# YTN1-E608_Key.net
KiCad netlist of a schematic drawn in Altium Designer
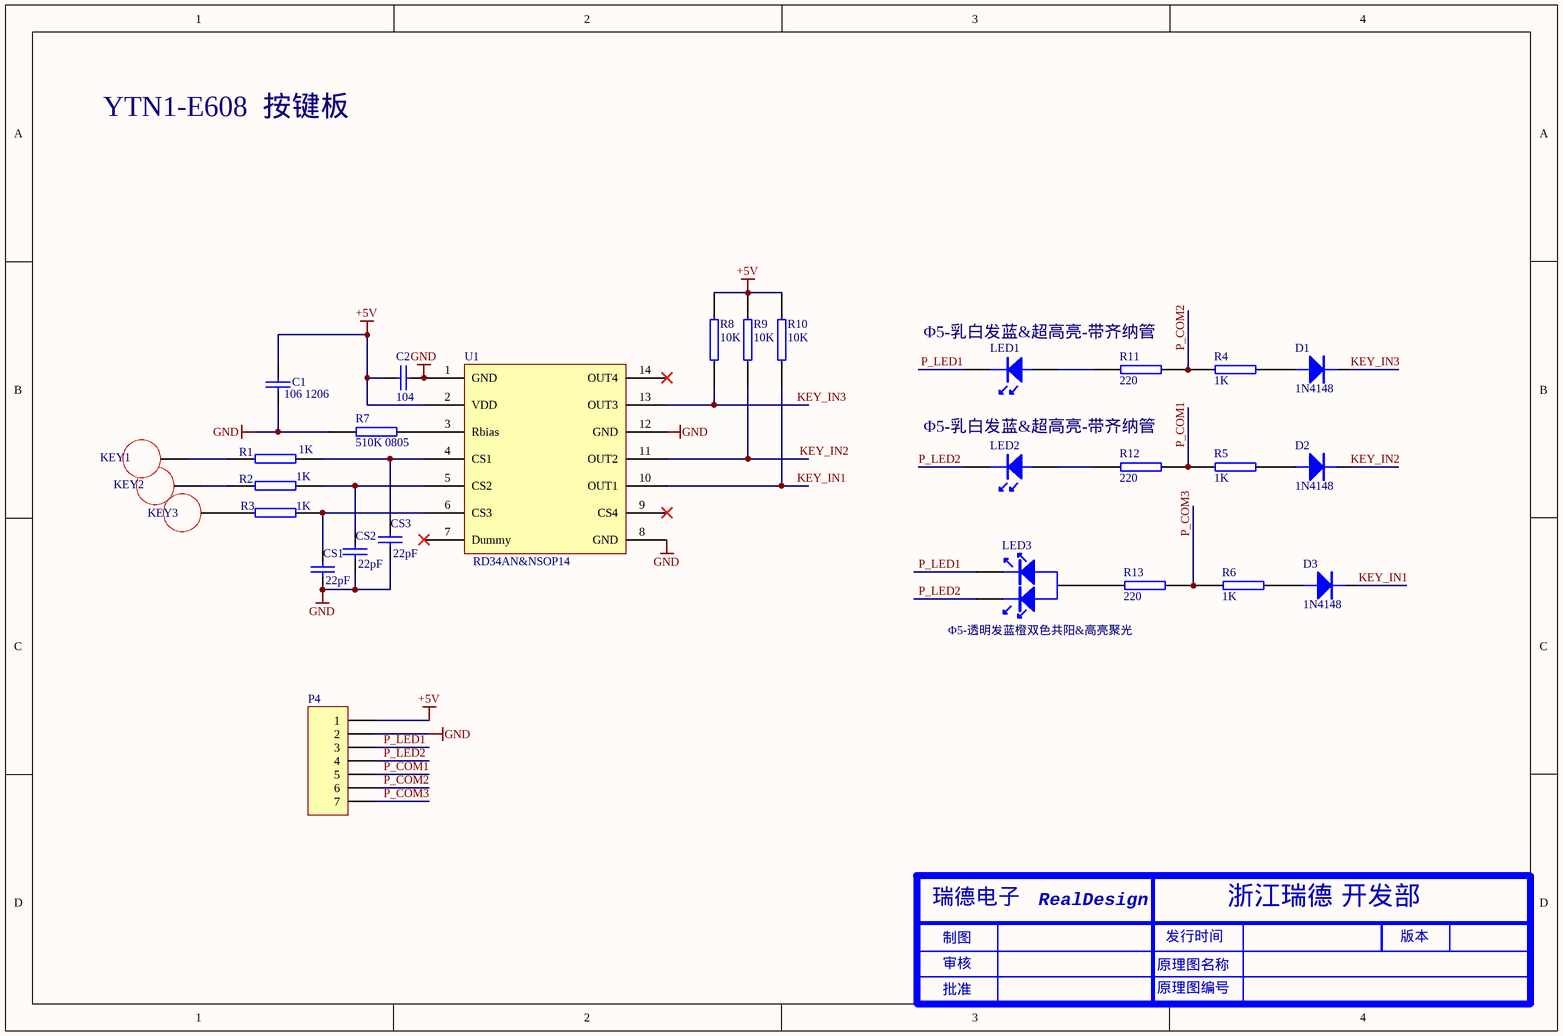
[diagram p0: YTN1-E608(Key)按键板..schdoc]

(export (version "E")
  (design (tool "Eeschema 10.0.6"))
  (components
    (comp (ref "C1") (value "106 1206") (libsource (lib "*") (part "CAP")))
    (comp (ref "C2") (value "104") (libsource (lib "*") (part "CAP")))
    (comp (ref "CS1") (value "22pF") (libsource (lib "*") (part "CAP")))
    (comp (ref "CS2") (value "22pF") (libsource (lib "*") (part "CAP")))
    (comp (ref "CS3") (value "22pF") (libsource (lib "*") (part "CAP")))
    (comp (ref "D1") (value "1N4148") (libsource (lib "*") (part "D4007")))
    (comp (ref "D2") (value "1N4148") (libsource (lib "*") (part "D4007")))
    (comp (ref "D3") (value "1N4148") (libsource (lib "*") (part "D4007")))
    (comp (ref "KEY1") (value "~") (footprint "7130A-K") (libsource (lib "*") (part "TPAD-2")))
    (comp (ref "KEY2") (value "~") (footprint "7130A-K") (libsource (lib "*") (part "TPAD-2")))
    (comp (ref "KEY3") (value "~") (footprint "7130A-K") (libsource (lib "*") (part "TPAD-2")))
    (comp (ref "LED1") (value "~") (footprint "LED5.0-AI1") (libsource (lib "*") (part "LED")))
    (comp (ref "LED2") (value "~") (footprint "LED5.0-AI1") (libsource (lib "*") (part "LED")))
    (comp (ref "LED3") (value "Φ5-透明发蓝橙双色共阳&高亮聚光") (libsource (lib "*") (part "共阳双色发光二极管")))
    (comp (ref "P4")
      (value "~")
      (footprint "HDR1X7")
      (description "Header, 7-Pin")
      (fields (field (name "PUBLISHER") "Altium Limited"))
      (libsource (lib "*") (part "Header 7"))
    )
    (comp (ref "R1") (value "1K") (libsource (lib "*") (part "R")))
    (comp (ref "R2") (value "1K") (libsource (lib "*") (part "R")))
    (comp (ref "R3") (value "1K") (libsource (lib "*") (part "R")))
    (comp (ref "R4") (value "1K") (libsource (lib "*") (part "R")))
    (comp (ref "R5") (value "1K") (libsource (lib "*") (part "R")))
    (comp (ref "R6") (value "1K") (libsource (lib "*") (part "R")))
    (comp (ref "R7") (value "510K 0805") (libsource (lib "*") (part "R")))
    (comp (ref "R8") (value "10K") (libsource (lib "*") (part "R")))
    (comp (ref "R9") (value "10K") (libsource (lib "*") (part "R")))
    (comp (ref "R10") (value "10K") (libsource (lib "*") (part "R")))
    (comp (ref "R11") (value "220") (libsource (lib "*") (part "RES2")))
    (comp (ref "R12") (value "220") (libsource (lib "*") (part "RES2")))
    (comp (ref "R13") (value "220") (libsource (lib "*") (part "R")))
    (comp (ref "U1")
      (value "RD34AN&NSOP14")
      (footprint "SOP14")
      (description "HT48R06A-1(16PIN)")
      (libsource (lib "*") (part "HT48R06A-1(16PIN)"))
    )
  )
  (nets
    (net (code "1") (name "+5V") (class "Default")
      (node (ref "C1") (pin "1") (pintype "passive"))
      (node (ref "C2") (pin "2") (pintype "passive"))
      (node (ref "P4") (pin "1") (pinfunction "1_1") (pintype "passive"))
      (node (ref "R10") (pin "2") (pinfunction "2_2") (pintype "passive"))
      (node (ref "R8") (pin "2") (pinfunction "2_2") (pintype "passive"))
      (node (ref "R9") (pin "2") (pinfunction "2_2") (pintype "passive"))
      (node (ref "U1") (pin "2") (pinfunction "VDD_2") (pintype "passive"))
    )
    (net (code "2") (name "/KEY_IN1") (class "Default")
      (node (ref "D3") (pin "K") (pinfunction "K_K") (pintype "passive"))
      (node (ref "R10") (pin "1") (pinfunction "1_1") (pintype "passive"))
      (node (ref "U1") (pin "10") (pinfunction "OUT1_10") (pintype "passive"))
    )
    (net (code "3") (name "/KEY_IN2") (class "Default")
      (node (ref "D2") (pin "K") (pinfunction "K_K") (pintype "passive"))
      (node (ref "R9") (pin "1") (pinfunction "1_1") (pintype "passive"))
      (node (ref "U1") (pin "11") (pinfunction "OUT2_11") (pintype "passive"))
    )
    (net (code "4") (name "/KEY_IN3") (class "Default")
      (node (ref "D1") (pin "K") (pinfunction "K_K") (pintype "passive"))
      (node (ref "R8") (pin "1") (pinfunction "1_1") (pintype "passive"))
      (node (ref "U1") (pin "13") (pinfunction "OUT3_13") (pintype "passive"))
    )
    (net (code "5") (name "/P_COM1") (class "Default")
      (node (ref "P4") (pin "5") (pinfunction "5_5") (pintype "passive"))
      (node (ref "R12") (pin "1") (pinfunction "1_1") (pintype "passive"))
      (node (ref "R5") (pin "1") (pinfunction "1_1") (pintype "passive"))
    )
    (net (code "6") (name "/P_COM2") (class "Default")
      (node (ref "P4") (pin "6") (pinfunction "6_6") (pintype "passive"))
      (node (ref "R11") (pin "1") (pinfunction "1_1") (pintype "passive"))
      (node (ref "R4") (pin "1") (pinfunction "1_1") (pintype "passive"))
    )
    (net (code "7") (name "/P_COM3") (class "Default")
      (node (ref "P4") (pin "7") (pinfunction "7_7") (pintype "passive"))
      (node (ref "R13") (pin "1") (pinfunction "1_1") (pintype "passive"))
      (node (ref "R6") (pin "1") (pinfunction "1_1") (pintype "passive"))
    )
    (net (code "8") (name "/P_LED1") (class "Default")
      (node (ref "LED1") (pin "K") (pinfunction "K_K") (pintype "passive"))
      (node (ref "LED3") (pin "K") (pinfunction "K_K") (pintype "passive"))
      (node (ref "P4") (pin "3") (pinfunction "3_3") (pintype "passive"))
    )
    (net (code "9") (name "/P_LED2") (class "Default")
      (node (ref "LED2") (pin "K") (pinfunction "K_K") (pintype "passive"))
      (node (ref "LED3") (pin "K") (pinfunction "K_K") (pintype "passive"))
      (node (ref "P4") (pin "4") (pinfunction "4_4") (pintype "passive"))
    )
    (net (code "10") (name "GND") (class "Default")
      (node (ref "C1") (pin "2") (pintype "passive"))
      (node (ref "C2") (pin "1") (pintype "passive"))
      (node (ref "CS1") (pin "2") (pintype "passive"))
      (node (ref "CS2") (pin "2") (pintype "passive"))
      (node (ref "CS3") (pin "2") (pintype "passive"))
      (node (ref "P4") (pin "2") (pinfunction "2_2") (pintype "passive"))
      (node (ref "R7") (pin "1") (pinfunction "1_1") (pintype "passive"))
      (node (ref "U1") (pin "1") (pinfunction "GND_1") (pintype "passive"))
      (node (ref "U1") (pin "12") (pinfunction "GND_12") (pintype "passive"))
      (node (ref "U1") (pin "8") (pinfunction "GND_8") (pintype "passive"))
    )
    (net (code "11") (name "Net-(D1-PadA)") (class "Default")
      (node (ref "D1") (pin "A") (pinfunction "A_A") (pintype "passive"))
      (node (ref "R4") (pin "2") (pinfunction "2_2") (pintype "passive"))
    )
    (net (code "12") (name "Net-(D2-PadA)") (class "Default")
      (node (ref "D2") (pin "A") (pinfunction "A_A") (pintype "passive"))
      (node (ref "R5") (pin "2") (pinfunction "2_2") (pintype "passive"))
    )
    (net (code "13") (name "Net-(D3-PadA)") (class "Default")
      (node (ref "D3") (pin "A") (pinfunction "A_A") (pintype "passive"))
      (node (ref "R6") (pin "2") (pinfunction "2_2") (pintype "passive"))
    )
    (net (code "14") (name "Net-(KEY1-Pad1)") (class "Default")
      (node (ref "KEY1") (pin "1") (pinfunction "1_1") (pintype "passive"))
      (node (ref "R1") (pin "1") (pinfunction "1_1") (pintype "passive"))
    )
    (net (code "15") (name "Net-(KEY2-Pad1)") (class "Default")
      (node (ref "KEY2") (pin "1") (pinfunction "1_1") (pintype "passive"))
      (node (ref "R2") (pin "1") (pinfunction "1_1") (pintype "passive"))
    )
    (net (code "16") (name "Net-(KEY3-Pad1)") (class "Default")
      (node (ref "KEY3") (pin "1") (pinfunction "1_1") (pintype "passive"))
      (node (ref "R3") (pin "1") (pinfunction "1_1") (pintype "passive"))
    )
    (net (code "17") (name "Net-(LED1-PadA)") (class "Default")
      (node (ref "LED1") (pin "A") (pinfunction "A_A") (pintype "passive"))
      (node (ref "R11") (pin "2") (pinfunction "2_2") (pintype "passive"))
    )
    (net (code "18") (name "Net-(LED2-PadA)") (class "Default")
      (node (ref "LED2") (pin "A") (pinfunction "A_A") (pintype "passive"))
      (node (ref "R12") (pin "2") (pinfunction "2_2") (pintype "passive"))
    )
    (net (code "19") (name "Net-(LED3-Pad0)") (class "Default")
      (node (ref "LED3") (pin "0") (pinfunction "0_0") (pintype "passive"))
      (node (ref "R13") (pin "2") (pinfunction "2_2") (pintype "passive"))
    )
    (net (code "20") (name "Net-(U1-CS1)") (class "Default")
      (node (ref "CS3") (pin "1") (pintype "passive"))
      (node (ref "R1") (pin "2") (pinfunction "2_2") (pintype "passive"))
      (node (ref "U1") (pin "4") (pinfunction "CS1_4") (pintype "passive"))
    )
    (net (code "21") (name "Net-(U1-CS2)") (class "Default")
      (node (ref "CS2") (pin "1") (pintype "passive"))
      (node (ref "R2") (pin "2") (pinfunction "2_2") (pintype "passive"))
      (node (ref "U1") (pin "5") (pinfunction "CS2_5") (pintype "passive"))
    )
    (net (code "22") (name "Net-(U1-CS3)") (class "Default")
      (node (ref "CS1") (pin "1") (pintype "passive"))
      (node (ref "R3") (pin "2") (pinfunction "2_2") (pintype "passive"))
      (node (ref "U1") (pin "6") (pinfunction "CS3_6") (pintype "passive"))
    )
    (net (code "23") (name "Net-(U1-Rbias)") (class "Default")
      (node (ref "R7") (pin "2") (pinfunction "2_2") (pintype "passive"))
      (node (ref "U1") (pin "3") (pinfunction "Rbias_3") (pintype "passive"))
    )
    (net (code "24") (name "unconnected-(U1-CS4-Pad9)") (class "Default")
      (node (ref "U1") (pin "9") (pinfunction "CS4_9") (pintype "passive+no_connect"))
    )
    (net (code "25") (name "unconnected-(U1-Dummy-Pad7)") (class "Default")
      (node (ref "U1") (pin "7") (pinfunction "Dummy_7") (pintype "passive+no_connect"))
    )
    (net (code "26") (name "unconnected-(U1-OUT4-Pad14)") (class "Default")
      (node (ref "U1") (pin "14") (pinfunction "OUT4_14") (pintype "passive+no_connect"))
    )
  )
)
